# PowerSupply.net
KiCad netlist of a schematic drawn in Altium Designer
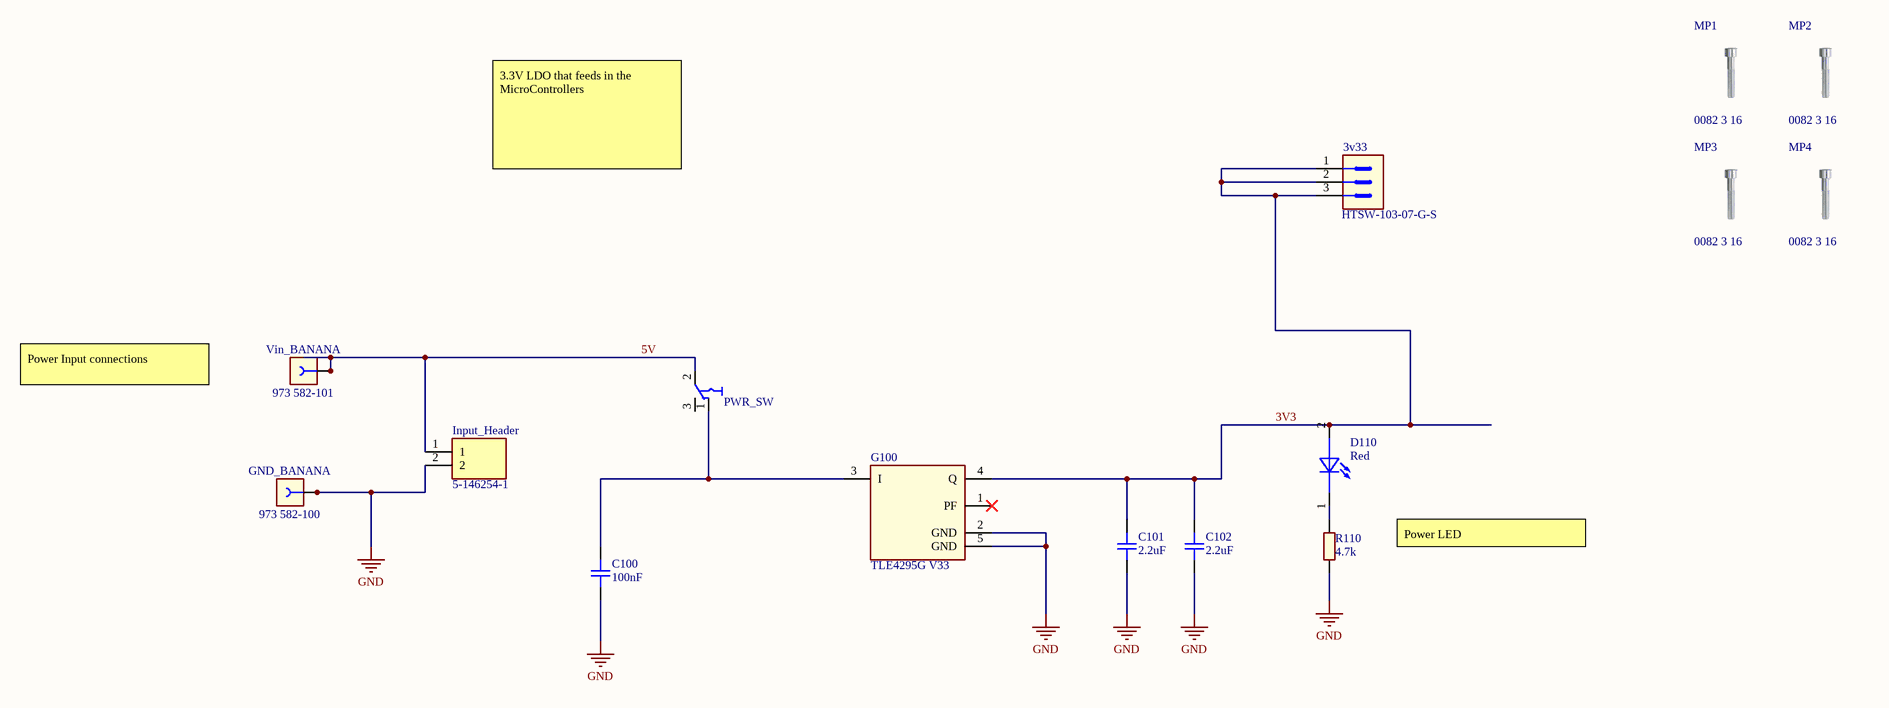
[diagram p0: PowerSupply.SchDoc]

(export (version "E")
  (design (tool "Eeschema 10.0.6"))
  (components
    (comp (ref "3v33")
      (value "HTSW-103-07-G-S")
      (footprint "CON-THT-2.54-3-1-8.38")
      (description "Through hole .025 SQ Post Header, 2.54mm pitch, 3 pin, vertical, single row")
      (fields (field (name "LEGACY PARTNUMBER") "CON00000054") (field (name "MANUFACTURER") "Samtec"))
      (libsource (lib "PCBLibraryData") (part "Header 3"))
    )
    (comp (ref "C100")
      (value "100nF")
      (footprint "CAPC1608X90N-2")
      (description "CAP / CERA / 100nF / 50V / 10% / X7R (EIA) / -55°C to 125°C / 0603 / SMD / -")
      (fields (field (name "MANUFACTURER") "AVX"))
      (libsource (lib "PCBLibraryData") (part "CAP-SGL-STD-02P_00000001"))
    )
    (comp (ref "C101")
      (value "2.2uF")
      (footprint "CAPC1608X90N-3")
      (description "CAP / CERA / 2.2uF / 25V / 10% / X5R (EIA) / -55°C to 85°C / 0603(1608) / SMD / -")
      (fields (field (name "LEGACY PARTNUMBER") "CAP01010924") (field (name "MANUFACTURER") "MuRata"))
      (libsource (lib "PCBLibraryData") (part "CAP-SGL-STD-02P_00000001"))
    )
    (comp (ref "C102")
      (value "2.2uF")
      (footprint "CAPC1608X90N-3")
      (description "CAP / CERA / 2.2uF / 25V / 10% / X5R (EIA) / -55°C to 85°C / 0603(1608) / SMD / -")
      (fields (field (name "LEGACY PARTNUMBER") "CAP01010924") (field (name "MANUFACTURER") "MuRata"))
      (libsource (lib "PCBLibraryData") (part "CAP-SGL-STD-02P_00000001"))
    )
    (comp (ref "D110")
      (value "Red")
      (footprint "LEDSC160X80X80-2N-1")
      (description "WL-SMCW SMT Mono-color Chip LED Waterclear, Red,630nm")
      (fields (field (name "MANUFACTURER") "Wurth Elektronik"))
      (libsource (lib "PCBLibraryData") (part "d_led_a"))
    )
    (comp (ref "G100")
      (value "TLE4295G V33")
      (footprint "IFX-PG-SCT595-5-2")
      (fields (field (name "MANUFACTURER") "Infineon Technologies"))
      (libsource (lib "PCBLibraryData") (part "TLE4285 G"))
    )
    (comp (ref "GND_BANANA")
      (value "973 582-100")
      (footprint "CON-THT-973 582- 100")
      (description "Banana Socket, black, 17.5mm Pitch")
      (fields
        (field (name "LEGACY PARTNUMBER") "CON01500045")
        (field (name "MANUFACTURER") "Hirschmann Test & Measurement")
      )
      (libsource (lib "PCBLibraryData") (part "soc_banana_2p"))
    )
    (comp (ref "Input_Header")
      (value "5-146254-1")
      (footprint "SamacSys:HDRV2W68P254_2X1_213X488X1045P")
      (description "Connector")
      (libsource (lib "*") (part "5-146254-1"))
    )
    (comp (ref "MP1")
      (value "0082 3 16")
      (footprint "SCREW_0082 3 16_NPTH")
      (description "Cheese Head Screw With Hexagon Socket, DIN 912 (ISO 4762), M3, 16mm length")
      (fields
        (field (name "LEGACY PARTNUMBER") "MEC10000167")
        (field (name "MANUFACTURER") "Wurth Elektronik")
      )
      (libsource (lib "PCBLibraryData") (part "Screw_0082 3 16"))
    )
    (comp (ref "MP2")
      (value "0082 3 16")
      (footprint "SCREW_0082 3 16_NPTH")
      (description "Cheese Head Screw With Hexagon Socket, DIN 912 (ISO 4762), M3, 16mm length")
      (fields
        (field (name "LEGACY PARTNUMBER") "MEC10000167")
        (field (name "MANUFACTURER") "Wurth Elektronik")
      )
      (libsource (lib "PCBLibraryData") (part "Screw_0082 3 16"))
    )
    (comp (ref "MP3")
      (value "0082 3 16")
      (footprint "SCREW_0082 3 16_NPTH")
      (description "Cheese Head Screw With Hexagon Socket, DIN 912 (ISO 4762), M3, 16mm length")
      (fields
        (field (name "LEGACY PARTNUMBER") "MEC10000167")
        (field (name "MANUFACTURER") "Wurth Elektronik")
      )
      (libsource (lib "PCBLibraryData") (part "Screw_0082 3 16"))
    )
    (comp (ref "MP4")
      (value "0082 3 16")
      (footprint "SCREW_0082 3 16_NPTH")
      (description "Cheese Head Screw With Hexagon Socket, DIN 912 (ISO 4762), M3, 16mm length")
      (fields
        (field (name "LEGACY PARTNUMBER") "MEC10000167")
        (field (name "MANUFACTURER") "Wurth Elektronik")
      )
      (libsource (lib "PCBLibraryData") (part "Screw_0082 3 16"))
    )
    (comp (ref "PWR_SW")
      (value "CL-SB-12A-01T")
      (footprint "SW-SMD-CL-SB-12A-01T")
      (description "Slid Switch, 12V, 200mA")
      (fields (field (name "MANUFACTURER") "NIDEC COPAL ELECTRONICS, Inc."))
      (libsource (lib "PCBLibraryData") (part "sw_co213_3p"))
    )
    (comp (ref "R110")
      (value "4.7k")
      (footprint "RESC1609X55N")
      (description "RES / STD / 4.7k / 100mW / 1% / 100ppm/K / -55°C to 155°C / 1.60mm L X 0.85mm W X 0.55mm H / - / -")
      (fields (field (name "MANUFACTURER") "Panasonic"))
      (libsource (lib "PCBLibraryData") (part "RES-SGL-STD-02P_00000006"))
    )
    (comp (ref "Vin_BANANA")
      (value "973 582-101")
      (footprint "CON-THT-973 582- 101")
      (description "Banana Socket, Red, 17.5mm Pitch")
      (fields
        (field (name "LEGACY PARTNUMBER") "CON01500041")
        (field (name "MANUFACTURER") "Hirschmann Test & Measurement")
      )
      (libsource (lib "PCBLibraryData") (part "soc_banana_2p"))
    )
  )
  (nets
    (net (code "1") (name "/3V3") (class "Default")
      (node (ref "3v33") (pin "1") (pinfunction "1_1") (pintype "passive"))
      (node (ref "3v33") (pin "2") (pinfunction "2_2") (pintype "passive"))
      (node (ref "3v33") (pin "3") (pinfunction "3_3") (pintype "passive"))
      (node (ref "C101") (pin "2") (pinfunction "2_2") (pintype "passive"))
      (node (ref "C102") (pin "2") (pinfunction "2_2") (pintype "passive"))
      (node (ref "D110") (pin "2") (pinfunction "Anode_2") (pintype "passive"))
      (node (ref "G100") (pin "4") (pinfunction "Q_4") (pintype "power_in"))
    )
    (net (code "2") (name "/5V") (class "Default")
      (node (ref "Input_Header") (pin "1") (pinfunction "1_1") (pintype "passive"))
      (node (ref "PWR_SW") (pin "2") (pinfunction "2_2") (pintype "passive"))
      (node (ref "Vin_BANANA") (pin "1") (pinfunction "1_1") (pintype "passive"))
      (node (ref "Vin_BANANA") (pin "2") (pinfunction "2_2") (pintype "passive"))
    )
    (net (code "3") (name "GND") (class "Default")
      (node (ref "C100") (pin "1") (pinfunction "1_1") (pintype "passive"))
      (node (ref "C101") (pin "1") (pinfunction "1_1") (pintype "passive"))
      (node (ref "C102") (pin "1") (pinfunction "1_1") (pintype "passive"))
      (node (ref "G100") (pin "2") (pinfunction "GND_2") (pintype "power_in"))
      (node (ref "G100") (pin "5") (pinfunction "GND_5") (pintype "power_in"))
      (node (ref "GND_BANANA") (pin "1") (pinfunction "1_1") (pintype "passive"))
      (node (ref "GND_BANANA") (pin "2") (pinfunction "2_2") (pintype "passive"))
      (node (ref "Input_Header") (pin "2") (pinfunction "2_2") (pintype "passive"))
      (node (ref "R110") (pin "1") (pinfunction "1_1") (pintype "passive"))
    )
    (net (code "4") (name "Net-(D110-Cathode)") (class "Default")
      (node (ref "D110") (pin "1") (pinfunction "Cathode_1") (pintype "passive"))
      (node (ref "R110") (pin "2") (pinfunction "2_2") (pintype "passive"))
    )
    (net (code "5") (name "Net-(G100-I)") (class "Default")
      (node (ref "C100") (pin "2") (pinfunction "2_2") (pintype "passive"))
      (node (ref "G100") (pin "3") (pinfunction "I_3") (pintype "power_in"))
      (node (ref "PWR_SW") (pin "1") (pinfunction "1_1") (pintype "passive"))
    )
    (net (code "6") (name "unconnected-(G100-PF-Pad1)") (class "Default")
      (node (ref "G100") (pin "1") (pinfunction "PF_1") (pintype "power_in+no_connect"))
    )
    (net (code "7") (name "unconnected-(PWR_SW-Pad3)") (class "Default")
      (node (ref "PWR_SW") (pin "3") (pinfunction "3_3") (pintype "passive"))
    )
  )
)
